# main_board.net
KiCad netlist of a schematic drawn in EAGLE
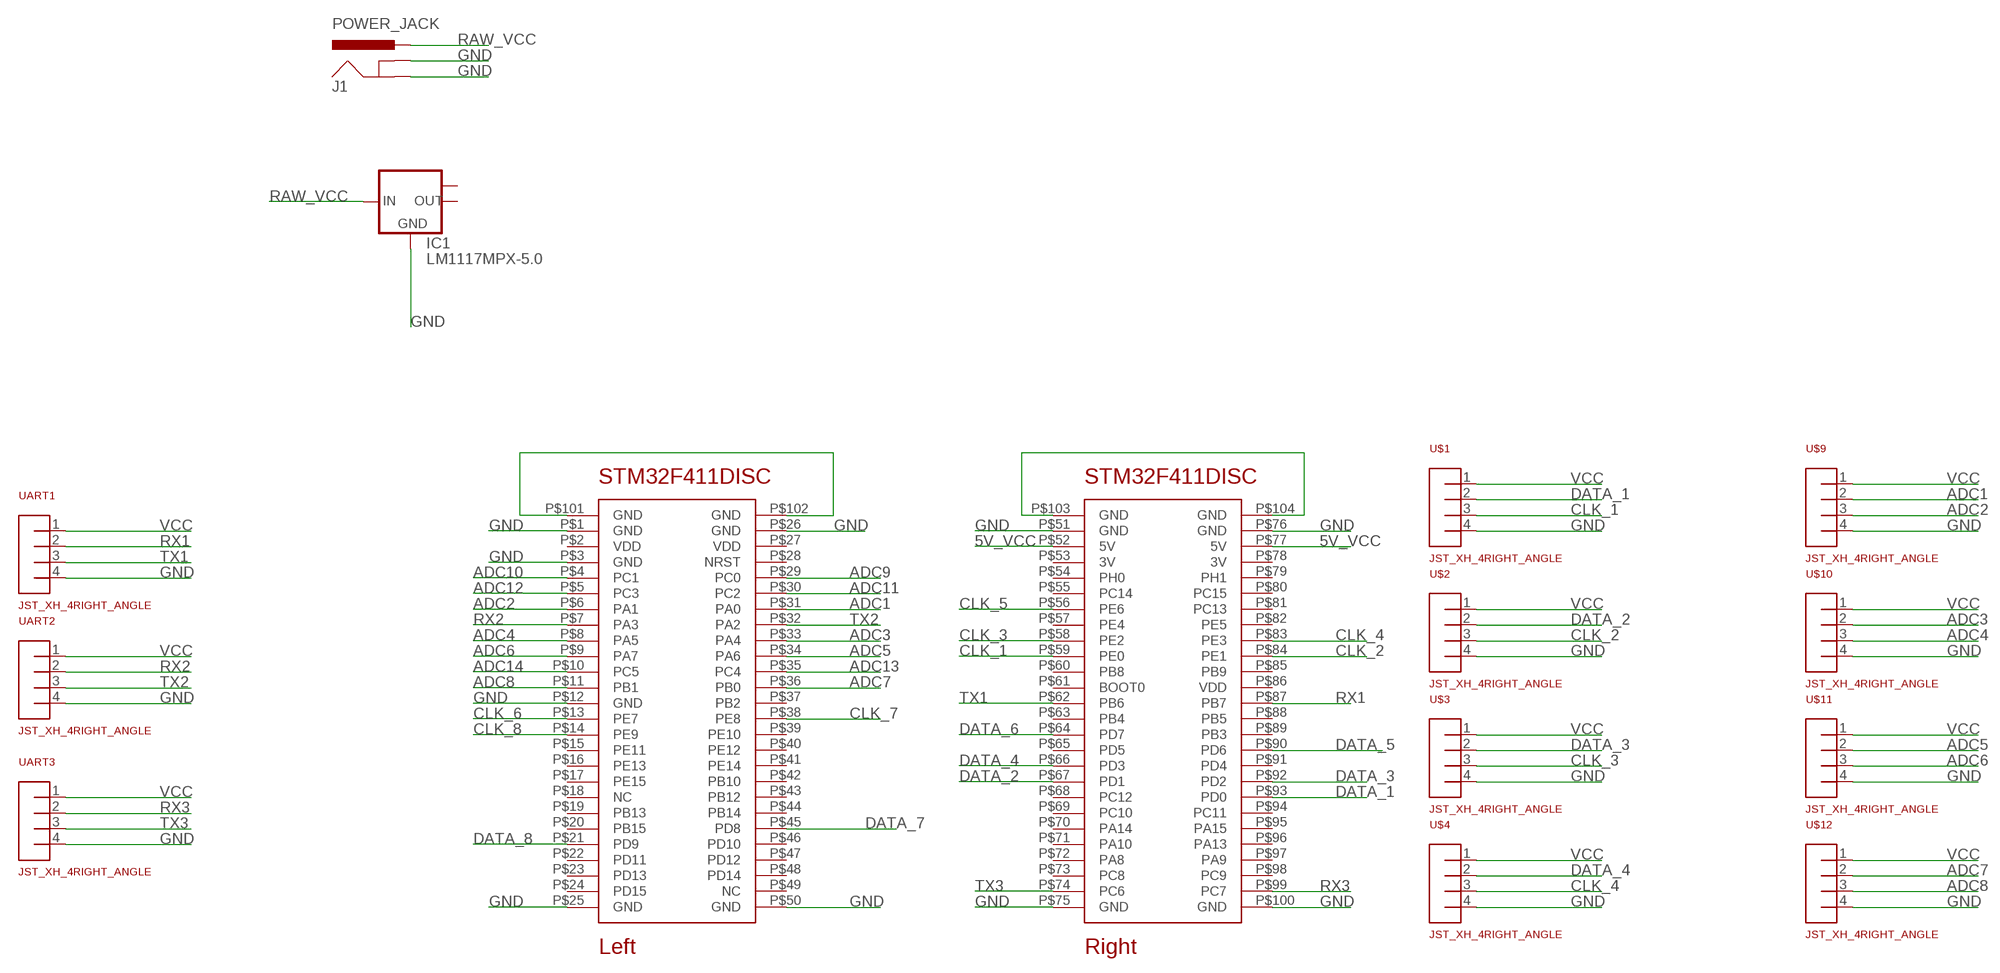
[diagram p0: schematic, sheet 1]

(export (version "E")
  (design (tool "Eeschema 10.0.6"))
  (components
    (comp (ref "IC1")
      (value "LM1117MPX-5.0")
      (footprint "eagle-import:SOT223")
      (libsource (lib "eagle-import") (part "LM1117MPX-5.0"))
    )
    (comp (ref "J1")
      (value "POWER_JACK")
      (footprint "eagle-import:POWER_JACK_PTH")
      (libsource (lib "eagle-import") (part "POWER_JACK"))
    )
    (comp (ref "STM32F411DISC")
      (value "STM32F411_DISCOVERY")
      (footprint "eagle-import:STM32F411_DISCOVERY")
      (libsource (lib "eagle-import") (part "STM32F411_DISCOVERY"))
    )
    (comp (ref "U$1")
      (value "JST_XH_4RIGHT_ANGLE")
      (footprint "eagle-import:JST_XH_4PIN_RIGHT_ANGLE")
      (libsource (lib "eagle-import") (part "JST_XH_4RIGHT_ANGLE"))
    )
    (comp (ref "U$2")
      (value "JST_XH_4RIGHT_ANGLE")
      (footprint "eagle-import:JST_XH_4PIN_RIGHT_ANGLE")
      (libsource (lib "eagle-import") (part "JST_XH_4RIGHT_ANGLE"))
    )
    (comp (ref "U$3")
      (value "JST_XH_4RIGHT_ANGLE")
      (footprint "eagle-import:JST_XH_4PIN_RIGHT_ANGLE")
      (libsource (lib "eagle-import") (part "JST_XH_4RIGHT_ANGLE"))
    )
    (comp (ref "U$4")
      (value "JST_XH_4RIGHT_ANGLE")
      (footprint "eagle-import:JST_XH_4PIN_RIGHT_ANGLE")
      (libsource (lib "eagle-import") (part "JST_XH_4RIGHT_ANGLE"))
    )
    (comp (ref "U$9")
      (value "JST_XH_4RIGHT_ANGLE")
      (footprint "eagle-import:JST_XH_4PIN_RIGHT_ANGLE")
      (libsource (lib "eagle-import") (part "JST_XH_4RIGHT_ANGLE"))
    )
    (comp (ref "U$10")
      (value "JST_XH_4RIGHT_ANGLE")
      (footprint "eagle-import:JST_XH_4PIN_RIGHT_ANGLE")
      (libsource (lib "eagle-import") (part "JST_XH_4RIGHT_ANGLE"))
    )
    (comp (ref "U$11")
      (value "JST_XH_4RIGHT_ANGLE")
      (footprint "eagle-import:JST_XH_4PIN_RIGHT_ANGLE")
      (libsource (lib "eagle-import") (part "JST_XH_4RIGHT_ANGLE"))
    )
    (comp (ref "U$12")
      (value "JST_XH_4RIGHT_ANGLE")
      (footprint "eagle-import:JST_XH_4PIN_RIGHT_ANGLE")
      (libsource (lib "eagle-import") (part "JST_XH_4RIGHT_ANGLE"))
    )
    (comp (ref "UART1")
      (value "JST_XH_4RIGHT_ANGLE")
      (footprint "eagle-import:JST_XH_4PIN_RIGHT_ANGLE")
      (libsource (lib "eagle-import") (part "JST_XH_4RIGHT_ANGLE"))
    )
    (comp (ref "UART2")
      (value "JST_XH_4RIGHT_ANGLE")
      (footprint "eagle-import:JST_XH_4PIN_RIGHT_ANGLE")
      (libsource (lib "eagle-import") (part "JST_XH_4RIGHT_ANGLE"))
    )
    (comp (ref "UART3")
      (value "JST_XH_4RIGHT_ANGLE")
      (footprint "eagle-import:JST_XH_4PIN_RIGHT_ANGLE")
      (libsource (lib "eagle-import") (part "JST_XH_4RIGHT_ANGLE"))
    )
  )
  (nets
    (net (code "1") (name "/5V_VCC") (class "Default")
      (node (ref "STM32F411DISC") (pin "P$52") (pinfunction "5V_P$52") (pintype "bidirectional"))
      (node (ref "STM32F411DISC") (pin "P$77") (pinfunction "5V_P$77") (pintype "bidirectional"))
    )
    (net (code "2") (name "/ADC1") (class "Default")
      (node (ref "STM32F411DISC") (pin "P$31") (pinfunction "PA0_P$31") (pintype "bidirectional"))
      (node (ref "U$9") (pin "2") (pinfunction "2_2") (pintype "bidirectional"))
    )
    (net (code "3") (name "/ADC2") (class "Default")
      (node (ref "STM32F411DISC") (pin "P$6") (pinfunction "PA1_P$6") (pintype "bidirectional"))
      (node (ref "U$9") (pin "3") (pinfunction "3_3") (pintype "bidirectional"))
    )
    (net (code "4") (name "/ADC3") (class "Default")
      (node (ref "STM32F411DISC") (pin "P$33") (pinfunction "PA4_P$33") (pintype "bidirectional"))
      (node (ref "U$10") (pin "2") (pinfunction "2_2") (pintype "bidirectional"))
    )
    (net (code "5") (name "/ADC4") (class "Default")
      (node (ref "STM32F411DISC") (pin "P$8") (pinfunction "PA5_P$8") (pintype "bidirectional"))
      (node (ref "U$10") (pin "3") (pinfunction "3_3") (pintype "bidirectional"))
    )
    (net (code "6") (name "/ADC5") (class "Default")
      (node (ref "STM32F411DISC") (pin "P$34") (pinfunction "PA6_P$34") (pintype "bidirectional"))
      (node (ref "U$11") (pin "2") (pinfunction "2_2") (pintype "bidirectional"))
    )
    (net (code "7") (name "/ADC6") (class "Default")
      (node (ref "STM32F411DISC") (pin "P$9") (pinfunction "PA7_P$9") (pintype "bidirectional"))
      (node (ref "U$11") (pin "3") (pinfunction "3_3") (pintype "bidirectional"))
    )
    (net (code "8") (name "/ADC7") (class "Default")
      (node (ref "STM32F411DISC") (pin "P$36") (pinfunction "PB0_P$36") (pintype "bidirectional"))
      (node (ref "U$12") (pin "2") (pinfunction "2_2") (pintype "bidirectional"))
    )
    (net (code "9") (name "/ADC8") (class "Default")
      (node (ref "STM32F411DISC") (pin "P$11") (pinfunction "PB1_P$11") (pintype "bidirectional"))
      (node (ref "U$12") (pin "3") (pinfunction "3_3") (pintype "bidirectional"))
    )
    (net (code "10") (name "/ADC9") (class "Default")
      (node (ref "STM32F411DISC") (pin "P$29") (pinfunction "PC0_P$29") (pintype "bidirectional"))
    )
    (net (code "11") (name "/ADC10") (class "Default")
      (node (ref "STM32F411DISC") (pin "P$4") (pinfunction "PC1_P$4") (pintype "bidirectional"))
    )
    (net (code "12") (name "/ADC11") (class "Default")
      (node (ref "STM32F411DISC") (pin "P$30") (pinfunction "PC2_P$30") (pintype "bidirectional"))
    )
    (net (code "13") (name "/ADC12") (class "Default")
      (node (ref "STM32F411DISC") (pin "P$5") (pinfunction "PC3_P$5") (pintype "bidirectional"))
    )
    (net (code "14") (name "/ADC13") (class "Default")
      (node (ref "STM32F411DISC") (pin "P$35") (pinfunction "PC4_P$35") (pintype "bidirectional"))
    )
    (net (code "15") (name "/ADC14") (class "Default")
      (node (ref "STM32F411DISC") (pin "P$10") (pinfunction "PC5_P$10") (pintype "bidirectional"))
    )
    (net (code "16") (name "/CLK_1") (class "Default")
      (node (ref "STM32F411DISC") (pin "P$59") (pinfunction "PE0_P$59") (pintype "bidirectional"))
      (node (ref "U$1") (pin "3") (pinfunction "3_3") (pintype "bidirectional"))
    )
    (net (code "17") (name "/CLK_2") (class "Default")
      (node (ref "STM32F411DISC") (pin "P$84") (pinfunction "PE1_P$84") (pintype "bidirectional"))
      (node (ref "U$2") (pin "3") (pinfunction "3_3") (pintype "bidirectional"))
    )
    (net (code "18") (name "/CLK_3") (class "Default")
      (node (ref "STM32F411DISC") (pin "P$58") (pinfunction "PE2_P$58") (pintype "bidirectional"))
      (node (ref "U$3") (pin "3") (pinfunction "3_3") (pintype "bidirectional"))
    )
    (net (code "19") (name "/CLK_4") (class "Default")
      (node (ref "STM32F411DISC") (pin "P$83") (pinfunction "PE3_P$83") (pintype "bidirectional"))
      (node (ref "U$4") (pin "3") (pinfunction "3_3") (pintype "bidirectional"))
    )
    (net (code "20") (name "/CLK_5") (class "Default")
      (node (ref "STM32F411DISC") (pin "P$56") (pinfunction "PE6_P$56") (pintype "bidirectional"))
    )
    (net (code "21") (name "/CLK_6") (class "Default")
      (node (ref "STM32F411DISC") (pin "P$13") (pinfunction "PE7_P$13") (pintype "bidirectional"))
    )
    (net (code "22") (name "/CLK_7") (class "Default")
      (node (ref "STM32F411DISC") (pin "P$38") (pinfunction "PE8_P$38") (pintype "bidirectional"))
    )
    (net (code "23") (name "/CLK_8") (class "Default")
      (node (ref "STM32F411DISC") (pin "P$14") (pinfunction "PE9_P$14") (pintype "bidirectional"))
    )
    (net (code "24") (name "/DATA_1") (class "Default")
      (node (ref "STM32F411DISC") (pin "P$93") (pinfunction "PD0_P$93") (pintype "bidirectional"))
      (node (ref "U$1") (pin "2") (pinfunction "2_2") (pintype "bidirectional"))
    )
    (net (code "25") (name "/DATA_2") (class "Default")
      (node (ref "STM32F411DISC") (pin "P$67") (pinfunction "PD1_P$67") (pintype "bidirectional"))
      (node (ref "U$2") (pin "2") (pinfunction "2_2") (pintype "bidirectional"))
    )
    (net (code "26") (name "/DATA_3") (class "Default")
      (node (ref "STM32F411DISC") (pin "P$92") (pinfunction "PD2_P$92") (pintype "bidirectional"))
      (node (ref "U$3") (pin "2") (pinfunction "2_2") (pintype "bidirectional"))
    )
    (net (code "27") (name "/DATA_4") (class "Default")
      (node (ref "STM32F411DISC") (pin "P$66") (pinfunction "PD3_P$66") (pintype "bidirectional"))
      (node (ref "U$4") (pin "2") (pinfunction "2_2") (pintype "bidirectional"))
    )
    (net (code "28") (name "/DATA_5") (class "Default")
      (node (ref "STM32F411DISC") (pin "P$90") (pinfunction "PD6_P$90") (pintype "bidirectional"))
    )
    (net (code "29") (name "/DATA_6") (class "Default")
      (node (ref "STM32F411DISC") (pin "P$64") (pinfunction "PD7_P$64") (pintype "bidirectional"))
    )
    (net (code "30") (name "/DATA_7") (class "Default")
      (node (ref "STM32F411DISC") (pin "P$45") (pinfunction "PD8_P$45") (pintype "bidirectional"))
    )
    (net (code "31") (name "/DATA_8") (class "Default")
      (node (ref "STM32F411DISC") (pin "P$21") (pinfunction "PD9_P$21") (pintype "bidirectional"))
    )
    (net (code "32") (name "/GND") (class "Default")
      (node (ref "IC1") (pin "1") (pinfunction "GND_1") (pintype "input"))
      (node (ref "J1") (pin "GND") (pinfunction "GND_GND") (pintype "bidirectional"))
      (node (ref "J1") (pin "GNDBREAK") (pinfunction "GNDBREAK_GNDBREAK") (pintype "bidirectional"))
      (node (ref "STM32F411DISC") (pin "P$1") (pinfunction "GND_P$1") (pintype "bidirectional"))
      (node (ref "STM32F411DISC") (pin "P$100") (pinfunction "GND_P$100") (pintype "bidirectional"))
      (node (ref "STM32F411DISC") (pin "P$12") (pinfunction "GND_P$12") (pintype "bidirectional"))
      (node (ref "STM32F411DISC") (pin "P$25") (pinfunction "GND_P$25") (pintype "bidirectional"))
      (node (ref "STM32F411DISC") (pin "P$26") (pinfunction "GND_P$26") (pintype "bidirectional"))
      (node (ref "STM32F411DISC") (pin "P$3") (pinfunction "GND_P$3") (pintype "bidirectional"))
      (node (ref "STM32F411DISC") (pin "P$50") (pinfunction "GND_P$50") (pintype "bidirectional"))
      (node (ref "STM32F411DISC") (pin "P$51") (pinfunction "GND_P$51") (pintype "bidirectional"))
      (node (ref "STM32F411DISC") (pin "P$75") (pinfunction "GND_P$75") (pintype "bidirectional"))
      (node (ref "STM32F411DISC") (pin "P$76") (pinfunction "GND_P$76") (pintype "bidirectional"))
      (node (ref "U$1") (pin "4") (pinfunction "4_4") (pintype "bidirectional"))
      (node (ref "U$10") (pin "4") (pinfunction "4_4") (pintype "bidirectional"))
      (node (ref "U$11") (pin "4") (pinfunction "4_4") (pintype "bidirectional"))
      (node (ref "U$12") (pin "4") (pinfunction "4_4") (pintype "bidirectional"))
      (node (ref "U$2") (pin "4") (pinfunction "4_4") (pintype "bidirectional"))
      (node (ref "U$3") (pin "4") (pinfunction "4_4") (pintype "bidirectional"))
      (node (ref "U$4") (pin "4") (pinfunction "4_4") (pintype "bidirectional"))
      (node (ref "U$9") (pin "4") (pinfunction "4_4") (pintype "bidirectional"))
      (node (ref "UART1") (pin "4") (pinfunction "4_4") (pintype "bidirectional"))
      (node (ref "UART2") (pin "4") (pinfunction "4_4") (pintype "bidirectional"))
      (node (ref "UART3") (pin "4") (pinfunction "4_4") (pintype "bidirectional"))
    )
    (net (code "33") (name "/RAW_VCC") (class "Default")
      (node (ref "IC1") (pin "3") (pinfunction "IN_3") (pintype "input"))
      (node (ref "J1") (pin "PWR") (pinfunction "PWR_PWR") (pintype "bidirectional"))
    )
    (net (code "34") (name "/RX1") (class "Default")
      (node (ref "STM32F411DISC") (pin "P$87") (pinfunction "PB7_P$87") (pintype "bidirectional"))
      (node (ref "UART1") (pin "2") (pinfunction "2_2") (pintype "bidirectional"))
    )
    (net (code "35") (name "/RX2") (class "Default")
      (node (ref "STM32F411DISC") (pin "P$7") (pinfunction "PA3_P$7") (pintype "bidirectional"))
      (node (ref "UART2") (pin "2") (pinfunction "2_2") (pintype "bidirectional"))
    )
    (net (code "36") (name "/RX3") (class "Default")
      (node (ref "STM32F411DISC") (pin "P$99") (pinfunction "PC7_P$99") (pintype "bidirectional"))
      (node (ref "UART3") (pin "2") (pinfunction "2_2") (pintype "bidirectional"))
    )
    (net (code "37") (name "/TX1") (class "Default")
      (node (ref "STM32F411DISC") (pin "P$62") (pinfunction "PB6_P$62") (pintype "bidirectional"))
      (node (ref "UART1") (pin "3") (pinfunction "3_3") (pintype "bidirectional"))
    )
    (net (code "38") (name "/TX2") (class "Default")
      (node (ref "STM32F411DISC") (pin "P$32") (pinfunction "PA2_P$32") (pintype "bidirectional"))
      (node (ref "UART2") (pin "3") (pinfunction "3_3") (pintype "bidirectional"))
    )
    (net (code "39") (name "/TX3") (class "Default")
      (node (ref "STM32F411DISC") (pin "P$74") (pinfunction "PC6_P$74") (pintype "bidirectional"))
      (node (ref "UART3") (pin "3") (pinfunction "3_3") (pintype "bidirectional"))
    )
    (net (code "40") (name "/VCC") (class "Default")
      (node (ref "U$1") (pin "1") (pinfunction "1_1") (pintype "bidirectional"))
      (node (ref "U$10") (pin "1") (pinfunction "1_1") (pintype "bidirectional"))
      (node (ref "U$11") (pin "1") (pinfunction "1_1") (pintype "bidirectional"))
      (node (ref "U$12") (pin "1") (pinfunction "1_1") (pintype "bidirectional"))
      (node (ref "U$2") (pin "1") (pinfunction "1_1") (pintype "bidirectional"))
      (node (ref "U$3") (pin "1") (pinfunction "1_1") (pintype "bidirectional"))
      (node (ref "U$4") (pin "1") (pinfunction "1_1") (pintype "bidirectional"))
      (node (ref "U$9") (pin "1") (pinfunction "1_1") (pintype "bidirectional"))
      (node (ref "UART1") (pin "1") (pinfunction "1_1") (pintype "bidirectional"))
      (node (ref "UART2") (pin "1") (pinfunction "1_1") (pintype "bidirectional"))
      (node (ref "UART3") (pin "1") (pinfunction "1_1") (pintype "bidirectional"))
    )
    (net (code "41") (name "Net-(STM32F411DISC-GND-PadP$101)") (class "Default")
      (node (ref "STM32F411DISC") (pin "P$101") (pinfunction "GND_P$101") (pintype "bidirectional"))
      (node (ref "STM32F411DISC") (pin "P$102") (pinfunction "GND_P$102") (pintype "bidirectional"))
    )
    (net (code "42") (name "Net-(STM32F411DISC-GND-PadP$103)") (class "Default")
      (node (ref "STM32F411DISC") (pin "P$103") (pinfunction "GND_P$103") (pintype "bidirectional"))
      (node (ref "STM32F411DISC") (pin "P$104") (pinfunction "GND_P$104") (pintype "bidirectional"))
    )
    (net (code "43") (name "unconnected-(IC1-OUT-Pad2)") (class "Default")
      (node (ref "IC1") (pin "2") (pinfunction "OUT_2") (pintype "passive"))
    )
    (net (code "44") (name "unconnected-(IC1-OUT1-PadTAB)") (class "Default")
      (node (ref "IC1") (pin "TAB") (pinfunction "OUT1_TAB") (pintype "passive"))
    )
    (net (code "45") (name "unconnected-(STM32F411DISC-3V-PadP$53)") (class "Default")
      (node (ref "STM32F411DISC") (pin "P$53") (pinfunction "3V_P$53") (pintype "bidirectional"))
    )
    (net (code "46") (name "unconnected-(STM32F411DISC-3V-PadP$78)") (class "Default")
      (node (ref "STM32F411DISC") (pin "P$78") (pinfunction "3V_P$78") (pintype "bidirectional"))
    )
    (net (code "47") (name "unconnected-(STM32F411DISC-BOOT0-PadP$61)") (class "Default")
      (node (ref "STM32F411DISC") (pin "P$61") (pinfunction "BOOT0_P$61") (pintype "bidirectional"))
    )
    (net (code "48") (name "unconnected-(STM32F411DISC-NC-PadP$18)") (class "Default")
      (node (ref "STM32F411DISC") (pin "P$18") (pinfunction "NC_P$18") (pintype "no_connect"))
    )
    (net (code "49") (name "unconnected-(STM32F411DISC-NC-PadP$49)") (class "Default")
      (node (ref "STM32F411DISC") (pin "P$49") (pinfunction "NC_P$49") (pintype "no_connect"))
    )
    (net (code "50") (name "unconnected-(STM32F411DISC-NRST-PadP$28)") (class "Default")
      (node (ref "STM32F411DISC") (pin "P$28") (pinfunction "NRST_P$28") (pintype "bidirectional"))
    )
    (net (code "51") (name "unconnected-(STM32F411DISC-PA8-PadP$72)") (class "Default")
      (node (ref "STM32F411DISC") (pin "P$72") (pinfunction "PA8_P$72") (pintype "bidirectional"))
    )
    (net (code "52") (name "unconnected-(STM32F411DISC-PA9-PadP$97)") (class "Default")
      (node (ref "STM32F411DISC") (pin "P$97") (pinfunction "PA9_P$97") (pintype "bidirectional"))
    )
    (net (code "53") (name "unconnected-(STM32F411DISC-PA10-PadP$71)") (class "Default")
      (node (ref "STM32F411DISC") (pin "P$71") (pinfunction "PA10_P$71") (pintype "bidirectional"))
    )
    (net (code "54") (name "unconnected-(STM32F411DISC-PA13-PadP$96)") (class "Default")
      (node (ref "STM32F411DISC") (pin "P$96") (pinfunction "PA13_P$96") (pintype "bidirectional"))
    )
    (net (code "55") (name "unconnected-(STM32F411DISC-PA14-PadP$70)") (class "Default")
      (node (ref "STM32F411DISC") (pin "P$70") (pinfunction "PA14_P$70") (pintype "bidirectional"))
    )
    (net (code "56") (name "unconnected-(STM32F411DISC-PA15-PadP$95)") (class "Default")
      (node (ref "STM32F411DISC") (pin "P$95") (pinfunction "PA15_P$95") (pintype "bidirectional"))
    )
    (net (code "57") (name "unconnected-(STM32F411DISC-PB2-PadP$37)") (class "Default")
      (node (ref "STM32F411DISC") (pin "P$37") (pinfunction "PB2_P$37") (pintype "bidirectional"))
    )
    (net (code "58") (name "unconnected-(STM32F411DISC-PB3-PadP$89)") (class "Default")
      (node (ref "STM32F411DISC") (pin "P$89") (pinfunction "PB3_P$89") (pintype "bidirectional"))
    )
    (net (code "59") (name "unconnected-(STM32F411DISC-PB4-PadP$63)") (class "Default")
      (node (ref "STM32F411DISC") (pin "P$63") (pinfunction "PB4_P$63") (pintype "bidirectional"))
    )
    (net (code "60") (name "unconnected-(STM32F411DISC-PB5-PadP$88)") (class "Default")
      (node (ref "STM32F411DISC") (pin "P$88") (pinfunction "PB5_P$88") (pintype "bidirectional"))
    )
    (net (code "61") (name "unconnected-(STM32F411DISC-PB8-PadP$60)") (class "Default")
      (node (ref "STM32F411DISC") (pin "P$60") (pinfunction "PB8_P$60") (pintype "bidirectional"))
    )
    (net (code "62") (name "unconnected-(STM32F411DISC-PB9-PadP$85)") (class "Default")
      (node (ref "STM32F411DISC") (pin "P$85") (pinfunction "PB9_P$85") (pintype "bidirectional"))
    )
    (net (code "63") (name "unconnected-(STM32F411DISC-PB10-PadP$42)") (class "Default")
      (node (ref "STM32F411DISC") (pin "P$42") (pinfunction "PB10_P$42") (pintype "bidirectional"))
    )
    (net (code "64") (name "unconnected-(STM32F411DISC-PB12-PadP$43)") (class "Default")
      (node (ref "STM32F411DISC") (pin "P$43") (pinfunction "PB12_P$43") (pintype "bidirectional"))
    )
    (net (code "65") (name "unconnected-(STM32F411DISC-PB13-PadP$19)") (class "Default")
      (node (ref "STM32F411DISC") (pin "P$19") (pinfunction "PB13_P$19") (pintype "bidirectional"))
    )
    (net (code "66") (name "unconnected-(STM32F411DISC-PB14-PadP$44)") (class "Default")
      (node (ref "STM32F411DISC") (pin "P$44") (pinfunction "PB14_P$44") (pintype "bidirectional"))
    )
    (net (code "67") (name "unconnected-(STM32F411DISC-PB15-PadP$20)") (class "Default")
      (node (ref "STM32F411DISC") (pin "P$20") (pinfunction "PB15_P$20") (pintype "bidirectional"))
    )
    (net (code "68") (name "unconnected-(STM32F411DISC-PC8-PadP$73)") (class "Default")
      (node (ref "STM32F411DISC") (pin "P$73") (pinfunction "PC8_P$73") (pintype "bidirectional"))
    )
    (net (code "69") (name "unconnected-(STM32F411DISC-PC9-PadP$98)") (class "Default")
      (node (ref "STM32F411DISC") (pin "P$98") (pinfunction "PC9_P$98") (pintype "bidirectional"))
    )
    (net (code "70") (name "unconnected-(STM32F411DISC-PC10-PadP$69)") (class "Default")
      (node (ref "STM32F411DISC") (pin "P$69") (pinfunction "PC10_P$69") (pintype "bidirectional"))
    )
    (net (code "71") (name "unconnected-(STM32F411DISC-PC11-PadP$94)") (class "Default")
      (node (ref "STM32F411DISC") (pin "P$94") (pinfunction "PC11_P$94") (pintype "bidirectional"))
    )
    (net (code "72") (name "unconnected-(STM32F411DISC-PC12-PadP$68)") (class "Default")
      (node (ref "STM32F411DISC") (pin "P$68") (pinfunction "PC12_P$68") (pintype "bidirectional"))
    )
    (net (code "73") (name "unconnected-(STM32F411DISC-PC13-PadP$81)") (class "Default")
      (node (ref "STM32F411DISC") (pin "P$81") (pinfunction "PC13_P$81") (pintype "bidirectional"))
    )
    (net (code "74") (name "unconnected-(STM32F411DISC-PC14-PadP$55)") (class "Default")
      (node (ref "STM32F411DISC") (pin "P$55") (pinfunction "PC14_P$55") (pintype "bidirectional"))
    )
    (net (code "75") (name "unconnected-(STM32F411DISC-PC15-PadP$80)") (class "Default")
      (node (ref "STM32F411DISC") (pin "P$80") (pinfunction "PC15_P$80") (pintype "bidirectional"))
    )
    (net (code "76") (name "unconnected-(STM32F411DISC-PD4-PadP$91)") (class "Default")
      (node (ref "STM32F411DISC") (pin "P$91") (pinfunction "PD4_P$91") (pintype "bidirectional"))
    )
    (net (code "77") (name "unconnected-(STM32F411DISC-PD5-PadP$65)") (class "Default")
      (node (ref "STM32F411DISC") (pin "P$65") (pinfunction "PD5_P$65") (pintype "bidirectional"))
    )
    (net (code "78") (name "unconnected-(STM32F411DISC-PD10-PadP$46)") (class "Default")
      (node (ref "STM32F411DISC") (pin "P$46") (pinfunction "PD10_P$46") (pintype "bidirectional"))
    )
    (net (code "79") (name "unconnected-(STM32F411DISC-PD11-PadP$22)") (class "Default")
      (node (ref "STM32F411DISC") (pin "P$22") (pinfunction "PD11_P$22") (pintype "bidirectional"))
    )
    (net (code "80") (name "unconnected-(STM32F411DISC-PD12-PadP$47)") (class "Default")
      (node (ref "STM32F411DISC") (pin "P$47") (pinfunction "PD12_P$47") (pintype "bidirectional"))
    )
    (net (code "81") (name "unconnected-(STM32F411DISC-PD13-PadP$23)") (class "Default")
      (node (ref "STM32F411DISC") (pin "P$23") (pinfunction "PD13_P$23") (pintype "bidirectional"))
    )
    (net (code "82") (name "unconnected-(STM32F411DISC-PD14-PadP$48)") (class "Default")
      (node (ref "STM32F411DISC") (pin "P$48") (pinfunction "PD14_P$48") (pintype "bidirectional"))
    )
    (net (code "83") (name "unconnected-(STM32F411DISC-PD15-PadP$24)") (class "Default")
      (node (ref "STM32F411DISC") (pin "P$24") (pinfunction "PD15_P$24") (pintype "bidirectional"))
    )
    (net (code "84") (name "unconnected-(STM32F411DISC-PE4-PadP$57)") (class "Default")
      (node (ref "STM32F411DISC") (pin "P$57") (pinfunction "PE4_P$57") (pintype "bidirectional"))
    )
    (net (code "85") (name "unconnected-(STM32F411DISC-PE5-PadP$82)") (class "Default")
      (node (ref "STM32F411DISC") (pin "P$82") (pinfunction "PE5_P$82") (pintype "bidirectional"))
    )
    (net (code "86") (name "unconnected-(STM32F411DISC-PE10-PadP$39)") (class "Default")
      (node (ref "STM32F411DISC") (pin "P$39") (pinfunction "PE10_P$39") (pintype "bidirectional"))
    )
    (net (code "87") (name "unconnected-(STM32F411DISC-PE11-PadP$15)") (class "Default")
      (node (ref "STM32F411DISC") (pin "P$15") (pinfunction "PE11_P$15") (pintype "bidirectional"))
    )
    (net (code "88") (name "unconnected-(STM32F411DISC-PE12-PadP$40)") (class "Default")
      (node (ref "STM32F411DISC") (pin "P$40") (pinfunction "PE12_P$40") (pintype "bidirectional"))
    )
    (net (code "89") (name "unconnected-(STM32F411DISC-PE13-PadP$16)") (class "Default")
      (node (ref "STM32F411DISC") (pin "P$16") (pinfunction "PE13_P$16") (pintype "bidirectional"))
    )
    (net (code "90") (name "unconnected-(STM32F411DISC-PE14-PadP$41)") (class "Default")
      (node (ref "STM32F411DISC") (pin "P$41") (pinfunction "PE14_P$41") (pintype "bidirectional"))
    )
    (net (code "91") (name "unconnected-(STM32F411DISC-PE15-PadP$17)") (class "Default")
      (node (ref "STM32F411DISC") (pin "P$17") (pinfunction "PE15_P$17") (pintype "bidirectional"))
    )
    (net (code "92") (name "unconnected-(STM32F411DISC-PH0-PadP$54)") (class "Default")
      (node (ref "STM32F411DISC") (pin "P$54") (pinfunction "PH0_P$54") (pintype "bidirectional"))
    )
    (net (code "93") (name "unconnected-(STM32F411DISC-PH1-PadP$79)") (class "Default")
      (node (ref "STM32F411DISC") (pin "P$79") (pinfunction "PH1_P$79") (pintype "bidirectional"))
    )
    (net (code "94") (name "unconnected-(STM32F411DISC-VDD-PadP$2)") (class "Default")
      (node (ref "STM32F411DISC") (pin "P$2") (pinfunction "VDD_P$2") (pintype "bidirectional"))
    )
    (net (code "95") (name "unconnected-(STM32F411DISC-VDD-PadP$27)") (class "Default")
      (node (ref "STM32F411DISC") (pin "P$27") (pinfunction "VDD_P$27") (pintype "bidirectional"))
    )
    (net (code "96") (name "unconnected-(STM32F411DISC-VDD-PadP$86)") (class "Default")
      (node (ref "STM32F411DISC") (pin "P$86") (pinfunction "VDD_P$86") (pintype "bidirectional"))
    )
  )
)
